# signal_interface_buffer1.net
KiCad netlist of a schematic drawn in EAGLE
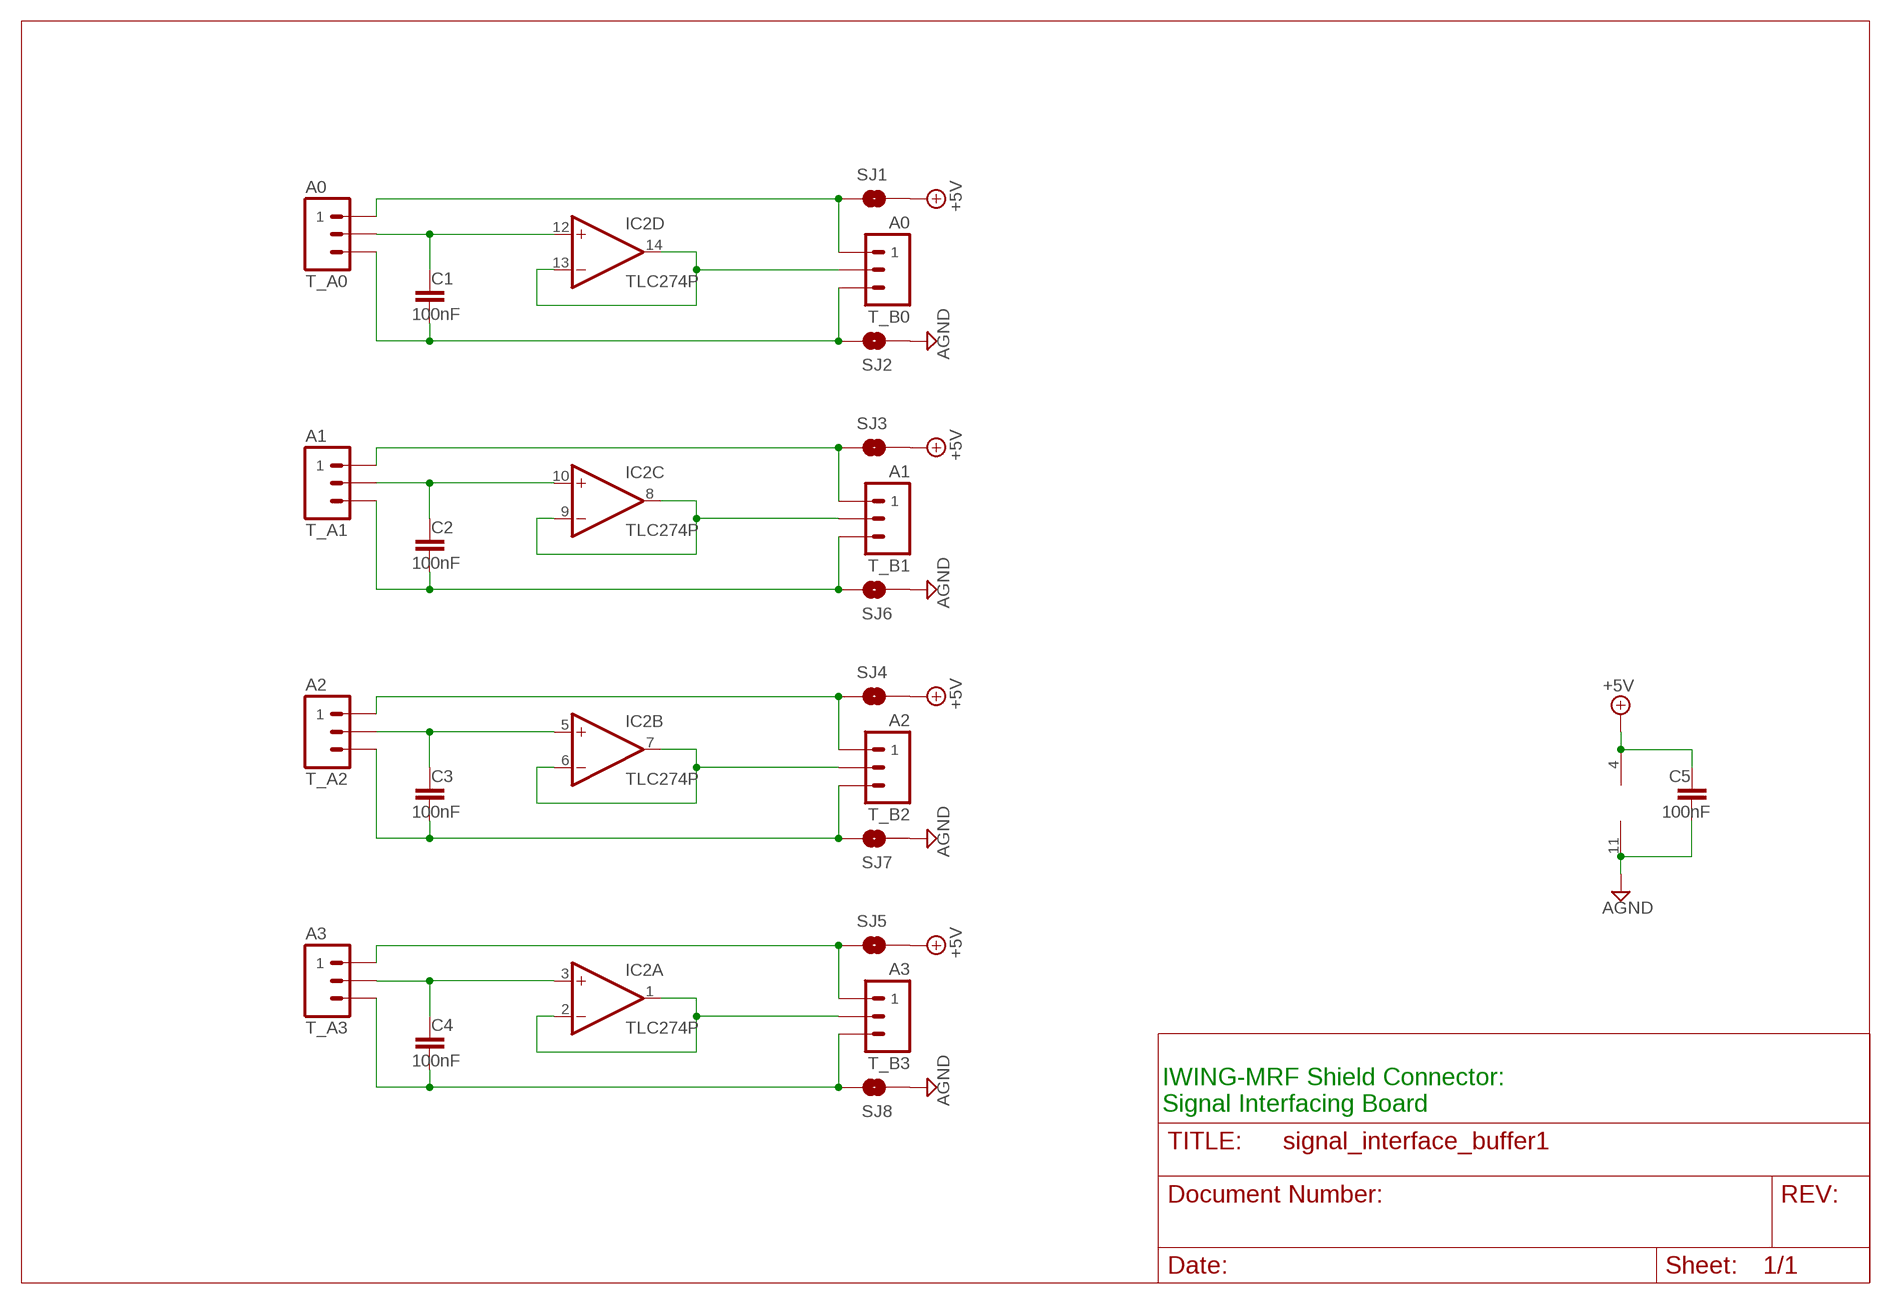
[diagram p0: schematic, sheet 1]

(export (version "E")
  (design (tool "Eeschema 10.0.6"))
  (components
    (comp (ref "C1")
      (value "100nF")
      (footprint "eagle-import:RCL_C050-025X075")
      (libsource (lib "eagle-import") (part "RCL_C-EU050-025X075"))
    )
    (comp (ref "C2")
      (value "100nF")
      (footprint "eagle-import:RCL_C050-025X075")
      (libsource (lib "eagle-import") (part "RCL_C-EU050-025X075"))
    )
    (comp (ref "C3")
      (value "100nF")
      (footprint "eagle-import:RCL_C050-025X075")
      (libsource (lib "eagle-import") (part "RCL_C-EU050-025X075"))
    )
    (comp (ref "C4")
      (value "100nF")
      (footprint "eagle-import:RCL_C050-025X075")
      (libsource (lib "eagle-import") (part "RCL_C-EU050-025X075"))
    )
    (comp (ref "C5")
      (value "100nF")
      (footprint "eagle-import:RCL_C050-025X075")
      (libsource (lib "eagle-import") (part "RCL_C-EU050-025X075"))
    )
    (comp (ref "IC2")
      (value "TLC274P")
      (footprint "eagle-import:DIL14")
      (libsource (lib "eagle-import") (part "TLC274P"))
    )
    (comp (ref "SJ1")
      (value "SOLDERJUMPERTRACE")
      (footprint "eagle-import:SJ_2S-TRACE")
      (libsource (lib "eagle-import") (part "SOLDERJUMPERTRACE"))
    )
    (comp (ref "SJ2")
      (value "SOLDERJUMPERTRACE")
      (footprint "eagle-import:SJ_2S-TRACE")
      (libsource (lib "eagle-import") (part "SOLDERJUMPERTRACE"))
    )
    (comp (ref "SJ3")
      (value "SOLDERJUMPERTRACE")
      (footprint "eagle-import:SJ_2S-TRACE")
      (libsource (lib "eagle-import") (part "SOLDERJUMPERTRACE"))
    )
    (comp (ref "SJ4")
      (value "SOLDERJUMPERTRACE")
      (footprint "eagle-import:SJ_2S-TRACE")
      (libsource (lib "eagle-import") (part "SOLDERJUMPERTRACE"))
    )
    (comp (ref "SJ5")
      (value "SOLDERJUMPERTRACE")
      (footprint "eagle-import:SJ_2S-TRACE")
      (libsource (lib "eagle-import") (part "SOLDERJUMPERTRACE"))
    )
    (comp (ref "SJ6")
      (value "SOLDERJUMPERTRACE")
      (footprint "eagle-import:SJ_2S-TRACE")
      (libsource (lib "eagle-import") (part "SOLDERJUMPERTRACE"))
    )
    (comp (ref "SJ7")
      (value "SOLDERJUMPERTRACE")
      (footprint "eagle-import:SJ_2S-TRACE")
      (libsource (lib "eagle-import") (part "SOLDERJUMPERTRACE"))
    )
    (comp (ref "SJ8")
      (value "SOLDERJUMPERTRACE")
      (footprint "eagle-import:SJ_2S-TRACE")
      (libsource (lib "eagle-import") (part "SOLDERJUMPERTRACE"))
    )
    (comp (ref "T_A0")
      (value "A0")
      (footprint "eagle-import:ED350V-03P")
      (libsource (lib "eagle-import") (part "ST03-3.5MM"))
    )
    (comp (ref "T_A1")
      (value "A1")
      (footprint "eagle-import:ED350V-03P")
      (libsource (lib "eagle-import") (part "ST03-3.5MM"))
    )
    (comp (ref "T_A2")
      (value "A2")
      (footprint "eagle-import:ED350V-03P")
      (libsource (lib "eagle-import") (part "ST03-3.5MM"))
    )
    (comp (ref "T_A3")
      (value "A3")
      (footprint "eagle-import:ED350V-03P")
      (libsource (lib "eagle-import") (part "ST03-3.5MM"))
    )
    (comp (ref "T_B0")
      (value "A0")
      (footprint "eagle-import:EK500V-03P")
      (libsource (lib "eagle-import") (part "ST03-5MM"))
    )
    (comp (ref "T_B1")
      (value "A1")
      (footprint "eagle-import:EK500V-03P")
      (libsource (lib "eagle-import") (part "ST03-5MM"))
    )
    (comp (ref "T_B2")
      (value "A2")
      (footprint "eagle-import:EK500V-03P")
      (libsource (lib "eagle-import") (part "ST03-5MM"))
    )
    (comp (ref "T_B3")
      (value "A3")
      (footprint "eagle-import:EK500V-03P")
      (libsource (lib "eagle-import") (part "ST03-5MM"))
    )
  )
  (nets
    (net (code "1") (name "+5V") (class "Default")
      (node (ref "C5") (pin "1") (pinfunction "1_1") (pintype "passive"))
      (node (ref "IC2") (pin "4") (pinfunction "V+_4") (pintype "power_in"))
      (node (ref "SJ1") (pin "2") (pinfunction "2_2") (pintype "passive"))
      (node (ref "SJ3") (pin "2") (pinfunction "2_2") (pintype "passive"))
      (node (ref "SJ4") (pin "2") (pinfunction "2_2") (pintype "passive"))
      (node (ref "SJ5") (pin "2") (pinfunction "2_2") (pintype "passive"))
    )
    (net (code "2") (name "AGND") (class "Default")
      (node (ref "C5") (pin "2") (pinfunction "2_2") (pintype "passive"))
      (node (ref "IC2") (pin "11") (pinfunction "V-_11") (pintype "power_in"))
      (node (ref "SJ2") (pin "1") (pinfunction "1_1") (pintype "passive"))
      (node (ref "SJ6") (pin "1") (pinfunction "1_1") (pintype "passive"))
      (node (ref "SJ7") (pin "1") (pinfunction "1_1") (pintype "passive"))
      (node (ref "SJ8") (pin "1") (pinfunction "1_1") (pintype "passive"))
    )
    (net (code "3") (name "Net-(IC2A-+IN)") (class "Default")
      (node (ref "C4") (pin "1") (pinfunction "1_1") (pintype "passive"))
      (node (ref "IC2") (pin "3") (pinfunction "+IN_3") (pintype "input"))
      (node (ref "T_A3") (pin "P$2") (pinfunction "2_P$2") (pintype "passive"))
    )
    (net (code "4") (name "Net-(IC2A--IN)") (class "Default")
      (node (ref "IC2") (pin "1") (pinfunction "OUT_1") (pintype "output"))
      (node (ref "IC2") (pin "2") (pinfunction "-IN_2") (pintype "input"))
      (node (ref "T_B3") (pin "P$2") (pinfunction "2_P$2") (pintype "passive"))
    )
    (net (code "5") (name "Net-(IC2B-+IN)") (class "Default")
      (node (ref "C3") (pin "1") (pinfunction "1_1") (pintype "passive"))
      (node (ref "IC2") (pin "5") (pinfunction "+IN_5") (pintype "input"))
      (node (ref "T_A2") (pin "P$2") (pinfunction "2_P$2") (pintype "passive"))
    )
    (net (code "6") (name "Net-(IC2B--IN)") (class "Default")
      (node (ref "IC2") (pin "6") (pinfunction "-IN_6") (pintype "input"))
      (node (ref "IC2") (pin "7") (pinfunction "OUT_7") (pintype "output"))
      (node (ref "T_B2") (pin "P$2") (pinfunction "2_P$2") (pintype "passive"))
    )
    (net (code "7") (name "Net-(IC2C-+IN)") (class "Default")
      (node (ref "C2") (pin "1") (pinfunction "1_1") (pintype "passive"))
      (node (ref "IC2") (pin "10") (pinfunction "+IN_10") (pintype "input"))
      (node (ref "T_A1") (pin "P$2") (pinfunction "2_P$2") (pintype "passive"))
    )
    (net (code "8") (name "Net-(IC2C--IN)") (class "Default")
      (node (ref "IC2") (pin "8") (pinfunction "OUT_8") (pintype "output"))
      (node (ref "IC2") (pin "9") (pinfunction "-IN_9") (pintype "input"))
      (node (ref "T_B1") (pin "P$2") (pinfunction "2_P$2") (pintype "passive"))
    )
    (net (code "9") (name "Net-(IC2D-+IN)") (class "Default")
      (node (ref "C1") (pin "1") (pinfunction "1_1") (pintype "passive"))
      (node (ref "IC2") (pin "12") (pinfunction "+IN_12") (pintype "input"))
      (node (ref "T_A0") (pin "P$2") (pinfunction "2_P$2") (pintype "passive"))
    )
    (net (code "10") (name "Net-(IC2D--IN)") (class "Default")
      (node (ref "IC2") (pin "13") (pinfunction "-IN_13") (pintype "input"))
      (node (ref "IC2") (pin "14") (pinfunction "OUT_14") (pintype "output"))
      (node (ref "T_B0") (pin "P$2") (pinfunction "2_P$2") (pintype "passive"))
    )
    (net (code "11") (name "Net-(T_A0-1)") (class "Default")
      (node (ref "SJ1") (pin "1") (pinfunction "1_1") (pintype "passive"))
      (node (ref "T_A0") (pin "P$1") (pinfunction "1_P$1") (pintype "passive"))
      (node (ref "T_B0") (pin "P$1") (pinfunction "1_P$1") (pintype "passive"))
    )
    (net (code "12") (name "Net-(T_A0-3)") (class "Default")
      (node (ref "C1") (pin "2") (pinfunction "2_2") (pintype "passive"))
      (node (ref "SJ2") (pin "2") (pinfunction "2_2") (pintype "passive"))
      (node (ref "T_A0") (pin "P$3") (pinfunction "3_P$3") (pintype "passive"))
      (node (ref "T_B0") (pin "P$3") (pinfunction "3_P$3") (pintype "passive"))
    )
    (net (code "13") (name "Net-(T_A1-1)") (class "Default")
      (node (ref "SJ3") (pin "1") (pinfunction "1_1") (pintype "passive"))
      (node (ref "T_A1") (pin "P$1") (pinfunction "1_P$1") (pintype "passive"))
      (node (ref "T_B1") (pin "P$1") (pinfunction "1_P$1") (pintype "passive"))
    )
    (net (code "14") (name "Net-(T_A1-3)") (class "Default")
      (node (ref "C2") (pin "2") (pinfunction "2_2") (pintype "passive"))
      (node (ref "SJ6") (pin "2") (pinfunction "2_2") (pintype "passive"))
      (node (ref "T_A1") (pin "P$3") (pinfunction "3_P$3") (pintype "passive"))
      (node (ref "T_B1") (pin "P$3") (pinfunction "3_P$3") (pintype "passive"))
    )
    (net (code "15") (name "Net-(T_A2-1)") (class "Default")
      (node (ref "SJ4") (pin "1") (pinfunction "1_1") (pintype "passive"))
      (node (ref "T_A2") (pin "P$1") (pinfunction "1_P$1") (pintype "passive"))
      (node (ref "T_B2") (pin "P$1") (pinfunction "1_P$1") (pintype "passive"))
    )
    (net (code "16") (name "Net-(T_A2-3)") (class "Default")
      (node (ref "C3") (pin "2") (pinfunction "2_2") (pintype "passive"))
      (node (ref "SJ7") (pin "2") (pinfunction "2_2") (pintype "passive"))
      (node (ref "T_A2") (pin "P$3") (pinfunction "3_P$3") (pintype "passive"))
      (node (ref "T_B2") (pin "P$3") (pinfunction "3_P$3") (pintype "passive"))
    )
    (net (code "17") (name "Net-(T_A3-1)") (class "Default")
      (node (ref "SJ5") (pin "1") (pinfunction "1_1") (pintype "passive"))
      (node (ref "T_A3") (pin "P$1") (pinfunction "1_P$1") (pintype "passive"))
      (node (ref "T_B3") (pin "P$1") (pinfunction "1_P$1") (pintype "passive"))
    )
    (net (code "18") (name "Net-(T_A3-3)") (class "Default")
      (node (ref "C4") (pin "2") (pinfunction "2_2") (pintype "passive"))
      (node (ref "SJ8") (pin "2") (pinfunction "2_2") (pintype "passive"))
      (node (ref "T_A3") (pin "P$3") (pinfunction "3_P$3") (pintype "passive"))
      (node (ref "T_B3") (pin "P$3") (pinfunction "3_P$3") (pintype "passive"))
    )
  )
)
